# GuitarMultiEffect.net
KiCad netlist of a schematic drawn in EasyEDA Pro
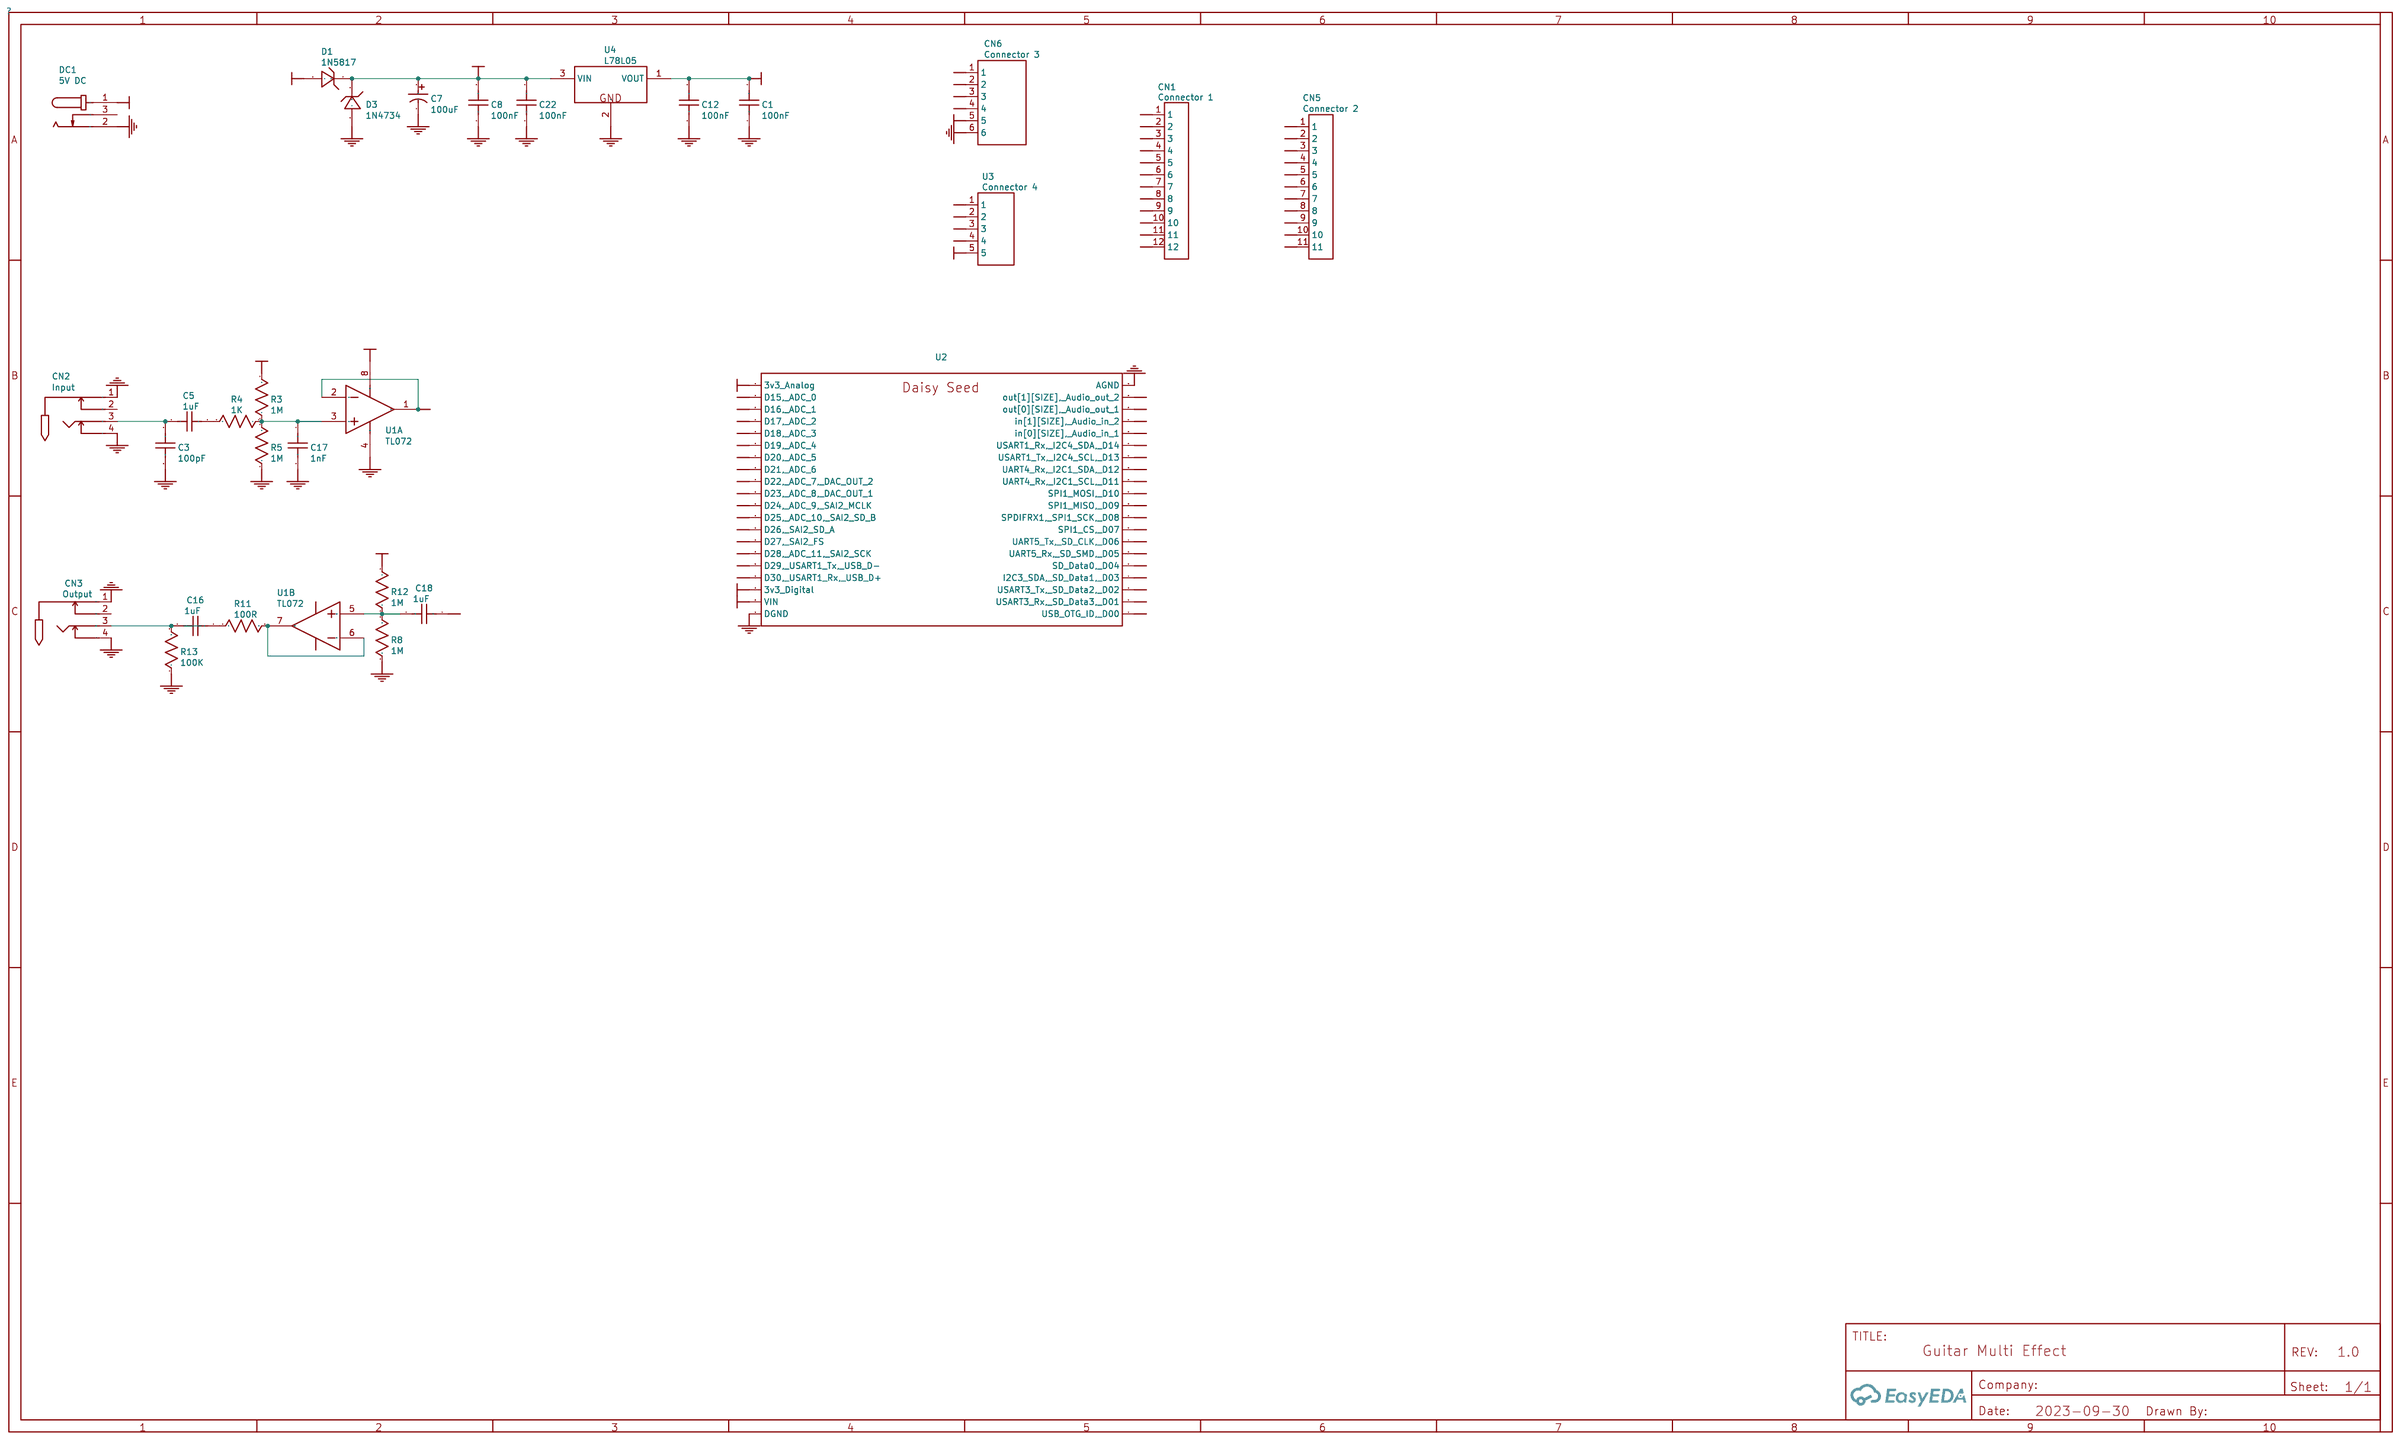
[diagram p0: schematic sheet]

(export (version "E")
  (design (tool "Eeschema 10.0.6"))
  (components
    (comp (ref "C1")
      (value "100nF")
      (footprint "easyedapro:CAP-TH_L8.0-W4.0-P5.00-D0.7")
      (fields
        (field (name "Manufacturer Part") "R08B1B102KN0B0S0N0")
        (field (name "Manufacturer") "STE(松田)")
        (field (name "Contributor") "LCSC")
      )
      (libsource (lib "easyedapro") (part "100nF"))
    )
    (comp (ref "C3")
      (value "100pF")
      (footprint "easyedapro:CAP-TH_L8.0-W4.0-P5.00-D0.7")
      (fields
        (field (name "Manufacturer Part") "R08B1B102KN0B0S0N0")
        (field (name "Manufacturer") "STE(松田)")
        (field (name "Contributor") "LCSC")
      )
      (libsource (lib "easyedapro") (part "100pF"))
    )
    (comp (ref "C5")
      (value "1uF")
      (footprint "easyedapro:CAP-TH_L8.0-W4.0-P5.00-D0.7")
      (fields
        (field (name "Manufacturer Part") "R08B1B102KN0B0S0N0")
        (field (name "Manufacturer") "STE(松田)")
        (field (name "Contributor") "LCSC")
      )
      (libsource (lib "easyedapro") (part "1uF"))
    )
    (comp (ref "C7")
      (value "100uF")
      (footprint "easyedapro:CAP-TH_BD5.0-P2.00-D0.8-FD")
      (fields
        (field (name "Manufacturer Part") "KM475M050D11RR0VH2FP0")
        (field (name "Manufacturer") "CX(承兴)")
      )
      (libsource (lib "easyedapro") (part "100uF"))
    )
    (comp (ref "C8")
      (value "100nF")
      (footprint "easyedapro:CAP-TH_L8.0-W4.0-P5.00-D0.7")
      (fields
        (field (name "Manufacturer Part") "R08B1B102KN0B0S0N0")
        (field (name "Manufacturer") "STE(松田)")
        (field (name "Contributor") "LCSC")
      )
      (libsource (lib "easyedapro") (part "100nF"))
    )
    (comp (ref "C12")
      (value "100nF")
      (footprint "easyedapro:CAP-TH_L8.0-W4.0-P5.00-D0.7")
      (fields
        (field (name "Manufacturer Part") "R08B1B102KN0B0S0N0")
        (field (name "Manufacturer") "STE(松田)")
        (field (name "Contributor") "LCSC")
      )
      (libsource (lib "easyedapro") (part "100nF"))
    )
    (comp (ref "C16")
      (value "1uF")
      (footprint "easyedapro:CAP-TH_L8.0-W4.0-P5.00-D0.7")
      (fields
        (field (name "Manufacturer Part") "R08B1B102KN0B0S0N0")
        (field (name "Manufacturer") "STE(松田)")
        (field (name "Contributor") "LCSC")
      )
      (libsource (lib "easyedapro") (part "1uF"))
    )
    (comp (ref "C17")
      (value "1nF")
      (footprint "easyedapro:CAP-TH_L8.0-W4.0-P5.00-D0.7")
      (fields
        (field (name "Manufacturer Part") "R08B1B102KN0B0S0N0")
        (field (name "Manufacturer") "STE(松田)")
        (field (name "Contributor") "LCSC")
      )
      (libsource (lib "easyedapro") (part "1nF"))
    )
    (comp (ref "C18")
      (value "1uF")
      (footprint "easyedapro:CAP-TH_L8.0-W4.0-P5.00-D0.7")
      (fields
        (field (name "Manufacturer Part") "R08B1B102KN0B0S0N0")
        (field (name "Manufacturer") "STE(松田)")
        (field (name "Contributor") "LCSC")
      )
      (libsource (lib "easyedapro") (part "1uF"))
    )
    (comp (ref "C22")
      (value "100nF")
      (footprint "easyedapro:CAP-TH_L8.0-W4.0-P5.00-D0.7")
      (fields
        (field (name "Manufacturer Part") "R08B1B102KN0B0S0N0")
        (field (name "Manufacturer") "STE(松田)")
        (field (name "Contributor") "LCSC")
      )
      (libsource (lib "easyedapro") (part "100nF"))
    )
    (comp (ref "CN1")
      (value "Connector 1")
      (footprint "easyedapro:CONN-TH_12P-P2.00_A2001WV-12P")
      (fields
        (field (name "Manufacturer Part") "A2001WV-12P")
        (field (name "Manufacturer") "CJT(长江连接器)")
        (field (name "Contributor") "LCSC")
      )
      (libsource (lib "easyedapro") (part "Connector 1"))
    )
    (comp (ref "CN2")
      (value "Input")
      (footprint "easyedapro:AUDIO-TH_CK6.35-3-15-6")
      (fields
        (field (name "Manufacturer Part") "CK6.35-3+15-6")
        (field (name "Manufacturer") "JINJIA(金佳)")
        (field (name "Contributor") "LCSC")
      )
      (libsource (lib "easyedapro") (part "Input"))
    )
    (comp (ref "CN3")
      (value "Output")
      (footprint "easyedapro:AUDIO-TH_CK6.35-3-15-6")
      (fields
        (field (name "Manufacturer Part") "CK6.35-3+15-6")
        (field (name "Manufacturer") "JINJIA(金佳)")
        (field (name "Contributor") "LCSC")
      )
      (libsource (lib "easyedapro") (part "Output"))
    )
    (comp (ref "CN5")
      (value "Connector 2")
      (footprint "easyedapro:CONN-TH_11P-P2.00_PH11A")
      (fields (field (name "Manufacturer Part") "PH-11A") (field (name "Manufacturer") "BOOMELE(博穆精密)"))
      (libsource (lib "easyedapro") (part "Connector 2"))
    )
    (comp (ref "CN6")
      (value "Connector 3")
      (footprint "easyedapro:CONN-TH_B06B-PASK-1-LF-SN")
      (fields
        (field (name "Manufacturer Part") "B06B-PASK-1(LF)(SN)")
        (field (name "Manufacturer") "JST")
        (field (name "Contributor") "LCSC")
      )
      (libsource (lib "easyedapro") (part "Connector 3"))
    )
    (comp (ref "D1")
      (value "1N5817")
      (footprint "easyedapro:DO-41_BD2.4-L4.7-P8.70-D0.9-RD")
      (fields (field (name "Manufacturer") "PINGWEI(平伟)") (field (name "Contributor") "LCSC"))
      (libsource (lib "easyedapro") (part "1N5817"))
    )
    (comp (ref "D3")
      (value "1N4734")
      (footprint "easyedapro:DO-41G_BD2.4-L4.0-P8.00-D0.7-RD")
      (fields
        (field (name "Manufacturer Part") "1N4734A-G_AY_10001")
        (field (name "Manufacturer") "PANJIT(强茂)")
        (field (name "Contributor") "LCSC")
      )
      (libsource (lib "easyedapro") (part "1N4734"))
    )
    (comp (ref "DC1")
      (value "5V DC")
      (footprint "easyedapro:CONN-TH_DC-005-2.5A-2.0")
      (fields
        (field (name "Manufacturer Part") "DC-005-2.5A-2.5")
        (field (name "Manufacturer") "XKB Connectivity(中国星坤)")
        (field (name "Contributor") "LCSC")
      )
      (libsource (lib "easyedapro") (part "5V DC"))
    )
    (comp (ref "R3")
      (value "1M")
      (footprint "easyedapro:PS-RES-16.5*6.42")
      (fields (field (name "Contributor") "LCEDA_Lib"))
      (libsource (lib "easyedapro") (part "1M"))
    )
    (comp (ref "R4")
      (value "1K")
      (footprint "easyedapro:PS-RES-16.5*6.42")
      (fields (field (name "Contributor") "LCEDA_Lib"))
      (libsource (lib "easyedapro") (part "1K"))
    )
    (comp (ref "R5")
      (value "1M")
      (footprint "easyedapro:PS-RES-16.5*6.42")
      (fields (field (name "Contributor") "LCEDA_Lib"))
      (libsource (lib "easyedapro") (part "1M"))
    )
    (comp (ref "R8")
      (value "1M")
      (footprint "easyedapro:PS-RES-16.5*6.42")
      (fields (field (name "Contributor") "LCEDA_Lib"))
      (libsource (lib "easyedapro") (part "1M"))
    )
    (comp (ref "R11")
      (value "100R")
      (footprint "easyedapro:PS-RES-16.5*6.42")
      (fields (field (name "Contributor") "LCEDA_Lib"))
      (libsource (lib "easyedapro") (part "100R"))
    )
    (comp (ref "R12")
      (value "1M")
      (footprint "easyedapro:PS-RES-16.5*6.42")
      (fields (field (name "Contributor") "LCEDA_Lib"))
      (libsource (lib "easyedapro") (part "1M"))
    )
    (comp (ref "R13")
      (value "100K")
      (footprint "easyedapro:PS-RES-16.5*6.42")
      (fields (field (name "Contributor") "LCEDA_Lib"))
      (libsource (lib "easyedapro") (part "100K"))
    )
    (comp (ref "U1")
      (value "TL072")
      (footprint "easyedapro:DIP-8_L9.7-W6.6-P2.54-LS7.6-BL")
      (fields (field (name "Manufacturer") "Gcore(扬州国芯)") (field (name "subpart_no") "1"))
      (libsource (lib "easyedapro") (part "TL072"))
    )
    (comp (ref "U2")
      (value "Daisy Seed")
      (footprint "easyedapro:DAISY_SEED")
      (fields (field (name "Contributor") "jjmens"))
      (libsource (lib "easyedapro") (part "Daisy Seed"))
    )
    (comp (ref "U3")
      (value "Connector 4")
      (footprint "easyedapro:CONN-TH_B5B-PH-K-S-LF-SN")
      (fields
        (field (name "Manufacturer Part") "B5B-PH-K-S(LF)(SN)")
        (field (name "Manufacturer") "JST")
        (field (name "Contributor") "LCSC")
      )
      (libsource (lib "easyedapro") (part "Connector 4"))
    )
    (comp (ref "U4")
      (value "L78L05")
      (footprint "easyedapro:TO-92-3_L4.9-W3.7-P1.27-L")
      (fields (field (name "Manufacturer Part") "L78L05ACZ") (field (name "Manufacturer") "ST(意法半导体)"))
      (libsource (lib "easyedapro") (part "L78L05"))
    )
  )
  (nets
    (net (code "1") (name "3V3A") (class "Default")
      (node (ref "CN6") (pin "5") (pinfunction "5_5") (pintype "unspecified"))
      (node (ref "U2") (pin "21") (pinfunction "3v3_Analog_21") (pintype "unspecified"))
    )
    (net (code "2") (name "3V3D") (class "Default")
      (node (ref "U2") (pin "38") (pinfunction "3v3_Digital_38") (pintype "unspecified"))
      (node (ref "U3") (pin "5") (pinfunction "5_5") (pintype "unspecified"))
    )
    (net (code "3") (name "5V") (class "Default")
      (node (ref "C1") (pin "2") (pinfunction "2_2") (pintype "unspecified"))
      (node (ref "C12") (pin "2") (pinfunction "2_2") (pintype "unspecified"))
      (node (ref "R12") (pin "2") (pinfunction "2_2") (pintype "unspecified"))
      (node (ref "R3") (pin "2") (pinfunction "2_2") (pintype "unspecified"))
      (node (ref "U1") (pin "8") (pinfunction "VCC+_8") (pintype "unspecified"))
      (node (ref "U4") (pin "1") (pinfunction "VOUT_1") (pintype "unspecified"))
    )
    (net (code "4") (name "5VDCIN") (class "Default")
      (node (ref "D1") (pin "2") (pinfunction "A_2") (pintype "unspecified"))
      (node (ref "DC1") (pin "1") (pinfunction "1_1") (pintype "unspecified"))
    )
    (net (code "5") (name "A00{slash}D15") (class "Default")
      (node (ref "CN1") (pin "1") (pinfunction "1_1") (pintype "unspecified"))
      (node (ref "U2") (pin "22") (pinfunction "D15,_ADC_0_22") (pintype "bidirectional"))
    )
    (net (code "6") (name "A01{slash}D16") (class "Default")
      (node (ref "CN1") (pin "2") (pinfunction "2_2") (pintype "unspecified"))
      (node (ref "U2") (pin "23") (pinfunction "D16,_ADC_1_23") (pintype "bidirectional"))
    )
    (net (code "7") (name "A02{slash}D17") (class "Default")
      (node (ref "CN1") (pin "3") (pinfunction "3_3") (pintype "unspecified"))
      (node (ref "U2") (pin "24") (pinfunction "D17,_ADC_2_24") (pintype "bidirectional"))
    )
    (net (code "8") (name "A03{slash}D18") (class "Default")
      (node (ref "CN1") (pin "4") (pinfunction "4_4") (pintype "unspecified"))
      (node (ref "U2") (pin "25") (pinfunction "D18,_ADC_3_25") (pintype "bidirectional"))
    )
    (net (code "9") (name "A04{slash}D19") (class "Default")
      (node (ref "CN1") (pin "5") (pinfunction "5_5") (pintype "unspecified"))
      (node (ref "U2") (pin "26") (pinfunction "D19,_ADC_4_26") (pintype "bidirectional"))
    )
    (net (code "10") (name "A05{slash}D20") (class "Default")
      (node (ref "CN1") (pin "6") (pinfunction "6_6") (pintype "unspecified"))
      (node (ref "U2") (pin "27") (pinfunction "D20,_ADC_5_27") (pintype "bidirectional"))
    )
    (net (code "11") (name "A06{slash}D21") (class "Default")
      (node (ref "CN1") (pin "7") (pinfunction "7_7") (pintype "unspecified"))
      (node (ref "U2") (pin "28") (pinfunction "D21,_ADC_6_28") (pintype "bidirectional"))
    )
    (net (code "12") (name "A07{slash}D22") (class "Default")
      (node (ref "CN1") (pin "8") (pinfunction "8_8") (pintype "unspecified"))
      (node (ref "U2") (pin "29") (pinfunction "D22,_ADC_7,_DAC_OUT_2_29") (pintype "bidirectional"))
    )
    (net (code "13") (name "A08{slash}D23") (class "Default")
      (node (ref "CN1") (pin "9") (pinfunction "9_9") (pintype "unspecified"))
      (node (ref "U2") (pin "30") (pinfunction "D23,_ADC_8,_DAC_OUT_1_30") (pintype "bidirectional"))
    )
    (net (code "14") (name "A09{slash}D24") (class "Default")
      (node (ref "CN1") (pin "10") (pinfunction "10_10") (pintype "unspecified"))
      (node (ref "U2") (pin "31") (pinfunction "D24,_ADC_9,_SAI2_MCLK_31") (pintype "bidirectional"))
    )
    (net (code "15") (name "A10{slash}D25") (class "Default")
      (node (ref "CN1") (pin "11") (pinfunction "11_11") (pintype "unspecified"))
      (node (ref "U2") (pin "32") (pinfunction "D25,_ADC_10,_SAI2_SD_B_32") (pintype "bidirectional"))
    )
    (net (code "16") (name "A11{slash}D28") (class "Default")
      (node (ref "CN1") (pin "12") (pinfunction "12_12") (pintype "unspecified"))
      (node (ref "U2") (pin "35") (pinfunction "D28,_ADC_11,_SAI2_SCK_35") (pintype "bidirectional"))
    )
    (net (code "17") (name "D00") (class "Default")
      (node (ref "CN5") (pin "1") (pinfunction "1_1") (pintype "unspecified"))
      (node (ref "U2") (pin "1") (pinfunction "USB_OTG_ID,_D00_1") (pintype "bidirectional"))
    )
    (net (code "18") (name "D01") (class "Default")
      (node (ref "CN5") (pin "2") (pinfunction "2_2") (pintype "unspecified"))
      (node (ref "U2") (pin "2") (pinfunction "USART3_Rx,_SD_Data3,_D01_2") (pintype "bidirectional"))
    )
    (net (code "19") (name "D02") (class "Default")
      (node (ref "CN5") (pin "3") (pinfunction "3_3") (pintype "unspecified"))
      (node (ref "U2") (pin "3") (pinfunction "USART3_Tx,_SD_Data2,_D02_3") (pintype "bidirectional"))
    )
    (net (code "20") (name "D03") (class "Default")
      (node (ref "CN5") (pin "4") (pinfunction "4_4") (pintype "unspecified"))
      (node (ref "U2") (pin "4") (pinfunction "I2C3_SDA,_SD_Data1,_D03_4") (pintype "bidirectional"))
    )
    (net (code "21") (name "D04") (class "Default")
      (node (ref "CN5") (pin "5") (pinfunction "5_5") (pintype "unspecified"))
      (node (ref "U2") (pin "5") (pinfunction "SD_Data0,_D04_5") (pintype "bidirectional"))
    )
    (net (code "22") (name "D05") (class "Default")
      (node (ref "CN5") (pin "6") (pinfunction "6_6") (pintype "unspecified"))
      (node (ref "U2") (pin "6") (pinfunction "UART5_Rx,_SD_SMD,_D05_6") (pintype "bidirectional"))
    )
    (net (code "23") (name "D06") (class "Default")
      (node (ref "CN5") (pin "7") (pinfunction "7_7") (pintype "unspecified"))
      (node (ref "U2") (pin "7") (pinfunction "UART5_Tx,_SD_CLK,_D06_7") (pintype "bidirectional"))
    )
    (net (code "24") (name "D07") (class "Default")
      (node (ref "CN5") (pin "8") (pinfunction "8_8") (pintype "unspecified"))
      (node (ref "U2") (pin "8") (pinfunction "SPI1_CS,_D07_8") (pintype "bidirectional"))
    )
    (net (code "25") (name "D08") (class "Default")
      (node (ref "CN5") (pin "9") (pinfunction "9_9") (pintype "unspecified"))
      (node (ref "U2") (pin "9") (pinfunction "SPDIFRX1,_SPI1_SCK,_D08_9") (pintype "bidirectional"))
    )
    (net (code "26") (name "D09") (class "Default")
      (node (ref "CN5") (pin "10") (pinfunction "10_10") (pintype "unspecified"))
      (node (ref "U2") (pin "10") (pinfunction "SPI1_MISO,_D09_10") (pintype "bidirectional"))
    )
    (net (code "27") (name "D10") (class "Default")
      (node (ref "CN5") (pin "11") (pinfunction "11_11") (pintype "unspecified"))
      (node (ref "U2") (pin "11") (pinfunction "SPI1_MOSI,_D10_11") (pintype "bidirectional"))
    )
    (net (code "28") (name "D11") (class "Default")
      (node (ref "CN6") (pin "1") (pinfunction "1_1") (pintype "unspecified"))
      (node (ref "U2") (pin "12") (pinfunction "UART4_Rx,_I2C1_SCL,_D11_12") (pintype "bidirectional"))
    )
    (net (code "29") (name "D12") (class "Default")
      (node (ref "CN6") (pin "2") (pinfunction "2_2") (pintype "unspecified"))
      (node (ref "U2") (pin "13") (pinfunction "UART4_Rx,_I2C1_SDA,_D12_13") (pintype "bidirectional"))
    )
    (net (code "30") (name "D13") (class "Default")
      (node (ref "CN6") (pin "3") (pinfunction "3_3") (pintype "unspecified"))
      (node (ref "U2") (pin "14") (pinfunction "USART1_Tx,_I2C4_SCL,_D13_14") (pintype "bidirectional"))
    )
    (net (code "31") (name "D14") (class "Default")
      (node (ref "CN6") (pin "4") (pinfunction "4_4") (pintype "unspecified"))
      (node (ref "U2") (pin "15") (pinfunction "USART1_Rx,_I2C4_SDA,_D14_15") (pintype "bidirectional"))
    )
    (net (code "32") (name "D26") (class "Default")
      (node (ref "U2") (pin "33") (pinfunction "D26,_SAI2_SD_A_33") (pintype "bidirectional"))
      (node (ref "U3") (pin "1") (pinfunction "1_1") (pintype "unspecified"))
    )
    (net (code "33") (name "D27") (class "Default")
      (node (ref "U2") (pin "34") (pinfunction "D27,_SAI2_FS_34") (pintype "bidirectional"))
      (node (ref "U3") (pin "2") (pinfunction "2_2") (pintype "unspecified"))
    )
    (net (code "34") (name "D29") (class "Default")
      (node (ref "U2") (pin "36") (pinfunction "D29,_USART1_Tx,_USB_D-_36") (pintype "bidirectional"))
      (node (ref "U3") (pin "3") (pinfunction "3_3") (pintype "unspecified"))
    )
    (net (code "35") (name "D30") (class "Default")
      (node (ref "U2") (pin "37") (pinfunction "D30,_USART1_Rx,_USB_D+_37") (pintype "bidirectional"))
      (node (ref "U3") (pin "4") (pinfunction "4_4") (pintype "unspecified"))
    )
    (net (code "36") (name "GND") (class "Default")
      (node (ref "C1") (pin "1") (pinfunction "1_1") (pintype "unspecified"))
      (node (ref "C12") (pin "1") (pinfunction "1_1") (pintype "unspecified"))
      (node (ref "C17") (pin "2") (pinfunction "2_2") (pintype "unspecified"))
      (node (ref "C22") (pin "1") (pinfunction "1_1") (pintype "unspecified"))
      (node (ref "C3") (pin "2") (pinfunction "2_2") (pintype "unspecified"))
      (node (ref "C7") (pin "2") (pinfunction "2_2") (pintype "input"))
      (node (ref "C8") (pin "1") (pinfunction "1_1") (pintype "unspecified"))
      (node (ref "CN2") (pin "1") (pinfunction "1_1") (pintype "input"))
      (node (ref "CN2") (pin "4") (pinfunction "4_4") (pintype "input"))
      (node (ref "CN3") (pin "1") (pinfunction "1_1") (pintype "input"))
      (node (ref "CN3") (pin "4") (pinfunction "4_4") (pintype "input"))
      (node (ref "CN6") (pin "6") (pinfunction "6_6") (pintype "unspecified"))
      (node (ref "D3") (pin "2") (pinfunction "A_2") (pintype "unspecified"))
      (node (ref "DC1") (pin "2") (pinfunction "2_2") (pintype "unspecified"))
      (node (ref "R13") (pin "1") (pinfunction "1_1") (pintype "unspecified"))
      (node (ref "R5") (pin "1") (pinfunction "1_1") (pintype "unspecified"))
      (node (ref "R8") (pin "1") (pinfunction "1_1") (pintype "unspecified"))
      (node (ref "U1") (pin "4") (pinfunction "VCC-_4") (pintype "unspecified"))
      (node (ref "U2") (pin "20") (pinfunction "AGND_20") (pintype "unspecified"))
      (node (ref "U2") (pin "40") (pinfunction "DGND_40") (pintype "unspecified"))
      (node (ref "U4") (pin "2") (pinfunction "GND_2") (pintype "unspecified"))
    )
    (net (code "37") (name "LINEINL") (class "Default")
      (node (ref "U1") (pin "1") (pinfunction "1OUT_1") (pintype "output"))
      (node (ref "U1") (pin "2") (pinfunction "1IN-_2") (pintype "unspecified"))
      (node (ref "U2") (pin "16") (pinfunction "in[0][SIZE],_Audio_in_1_16") (pintype "input"))
    )
    (net (code "38") (name "LINEINR") (class "Default")
      (node (ref "U2") (pin "17") (pinfunction "in[1][SIZE],_Audio_in_2_17") (pintype "input"))
    )
    (net (code "39") (name "LINEOUTL") (class "Default")
      (node (ref "C18") (pin "1") (pinfunction "1_1") (pintype "unspecified"))
      (node (ref "U2") (pin "18") (pinfunction "out[0][SIZE],_Audio_out_1_18") (pintype "output"))
    )
    (net (code "40") (name "LINEOUTR") (class "Default")
      (node (ref "U2") (pin "19") (pinfunction "out[1][SIZE],_Audio_out_2_19") (pintype "output"))
    )
    (net (code "41") (name "Net-(C3-Pad1)") (class "Default")
      (node (ref "C3") (pin "1") (pinfunction "1_1") (pintype "unspecified"))
      (node (ref "C5") (pin "1") (pinfunction "1_1") (pintype "unspecified"))
      (node (ref "CN2") (pin "3") (pinfunction "3_3") (pintype "input"))
    )
    (net (code "42") (name "Net-(C5-Pad2)") (class "Default")
      (node (ref "C5") (pin "2") (pinfunction "2_2") (pintype "unspecified"))
      (node (ref "R4") (pin "2") (pinfunction "2_2") (pintype "unspecified"))
    )
    (net (code "43") (name "Net-(C16-Pad1)") (class "Default")
      (node (ref "C16") (pin "1") (pinfunction "1_1") (pintype "unspecified"))
      (node (ref "R11") (pin "1") (pinfunction "1_1") (pintype "unspecified"))
    )
    (net (code "44") (name "Net-(C16-Pad2)") (class "Default")
      (node (ref "C16") (pin "2") (pinfunction "2_2") (pintype "unspecified"))
      (node (ref "CN3") (pin "3") (pinfunction "3_3") (pintype "input"))
      (node (ref "R13") (pin "2") (pinfunction "2_2") (pintype "unspecified"))
    )
    (net (code "45") (name "Net-(U1A-1IN+)") (class "Default")
      (node (ref "C17") (pin "1") (pinfunction "1_1") (pintype "unspecified"))
      (node (ref "R3") (pin "1") (pinfunction "1_1") (pintype "unspecified"))
      (node (ref "R4") (pin "1") (pinfunction "1_1") (pintype "unspecified"))
      (node (ref "R5") (pin "2") (pinfunction "2_2") (pintype "unspecified"))
      (node (ref "U1") (pin "3") (pinfunction "1IN+_3") (pintype "unspecified"))
    )
    (net (code "46") (name "Net-(U1B-2IN+)") (class "Default")
      (node (ref "C18") (pin "2") (pinfunction "2_2") (pintype "unspecified"))
      (node (ref "R12") (pin "1") (pinfunction "1_1") (pintype "unspecified"))
      (node (ref "R8") (pin "2") (pinfunction "2_2") (pintype "unspecified"))
      (node (ref "U1") (pin "5") (pinfunction "2IN+_5") (pintype "unspecified"))
    )
    (net (code "47") (name "Net-(U1B-2IN-)") (class "Default")
      (node (ref "R11") (pin "2") (pinfunction "2_2") (pintype "unspecified"))
      (node (ref "U1") (pin "6") (pinfunction "2IN-_6") (pintype "unspecified"))
      (node (ref "U1") (pin "7") (pinfunction "2OUT_7") (pintype "output"))
    )
    (net (code "48") (name "VCC") (class "Default")
      (node (ref "C22") (pin "2") (pinfunction "2_2") (pintype "unspecified"))
      (node (ref "C7") (pin "1") (pinfunction "1_1") (pintype "input"))
      (node (ref "C8") (pin "2") (pinfunction "2_2") (pintype "unspecified"))
      (node (ref "D1") (pin "1") (pinfunction "C_1") (pintype "unspecified"))
      (node (ref "D3") (pin "1") (pinfunction "C_1") (pintype "unspecified"))
      (node (ref "U2") (pin "39") (pinfunction "VIN_39") (pintype "unspecified"))
      (node (ref "U4") (pin "3") (pinfunction "VIN_3") (pintype "unspecified"))
    )
    (net (code "49") (name "unconnected-(CN2-Pad2)") (class "Default")
      (node (ref "CN2") (pin "2") (pinfunction "2_2") (pintype "input"))
    )
    (net (code "50") (name "unconnected-(CN3-Pad2)") (class "Default")
      (node (ref "CN3") (pin "2") (pinfunction "2_2") (pintype "input"))
    )
    (net (code "51") (name "unconnected-(DC1-Pad3)") (class "Default")
      (node (ref "DC1") (pin "3") (pinfunction "3_3") (pintype "unspecified"))
    )
  )
)
